# Single_Socket_TEMPORARY.net
KiCad netlist of a schematic drawn in EAGLE
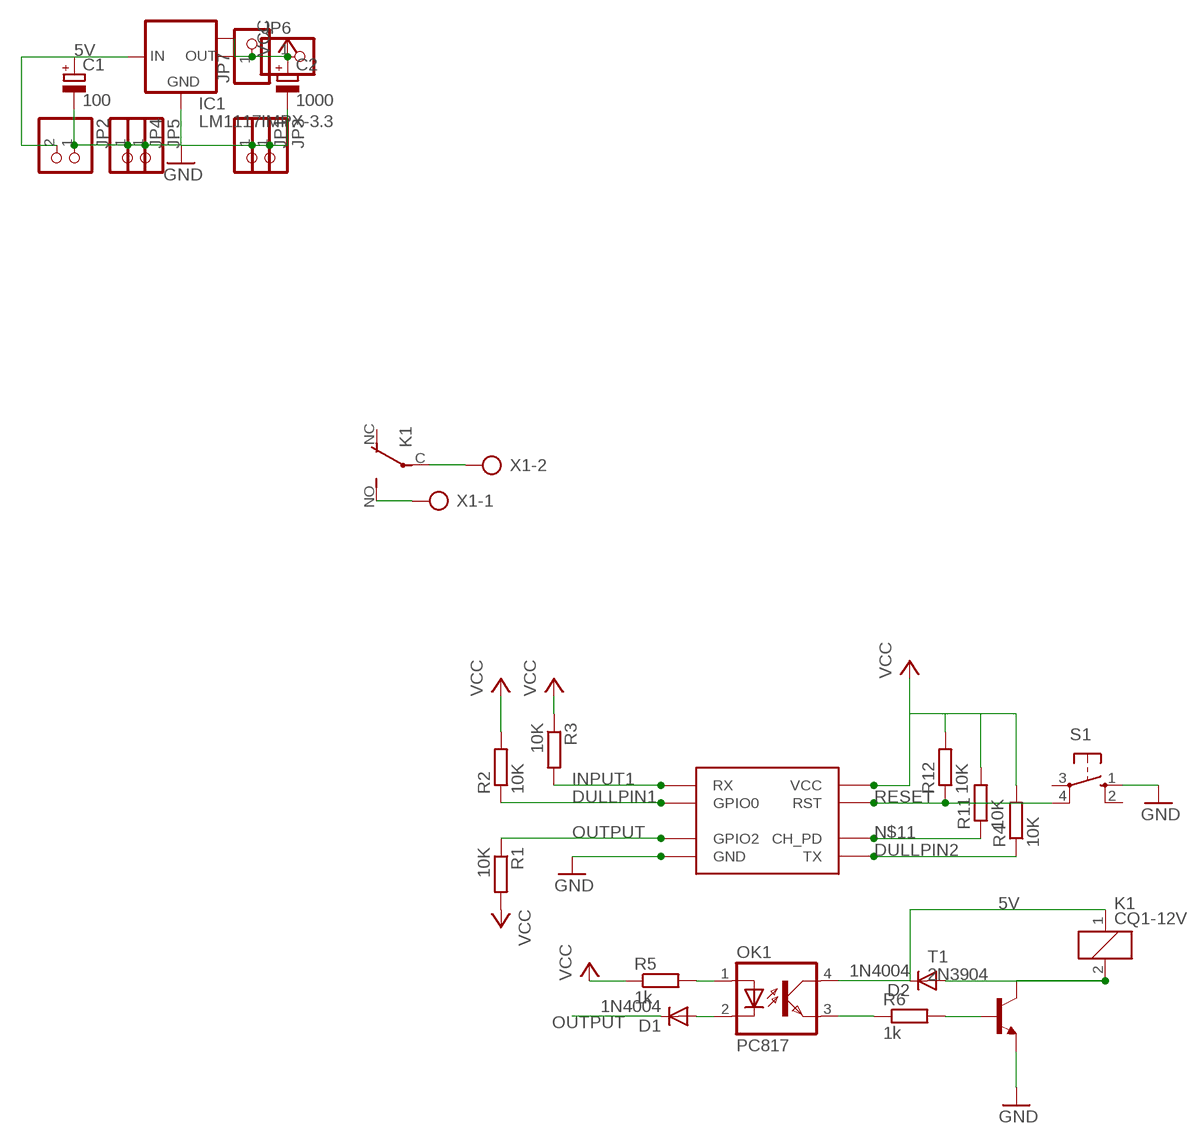
[diagram p0: schematic, sheet 1]

(export (version "E")
  (design (tool "Eeschema 10.0.6"))
  (components
    (comp (ref "C1")
      (value "100")
      (footprint "eagle-import:E5-10,5")
      (libsource (lib "eagle-import") (part "CPOL-EUE5-10.5"))
    )
    (comp (ref "C2")
      (value "1000")
      (footprint "eagle-import:E5-10,5")
      (libsource (lib "eagle-import") (part "CPOL-EUE5-10.5"))
    )
    (comp (ref "D1")
      (value "1N4004")
      (footprint "eagle-import:DO41-10")
      (libsource (lib "eagle-import") (part "1N4004"))
    )
    (comp (ref "D2")
      (value "1N4004")
      (footprint "eagle-import:DO41-10")
      (libsource (lib "eagle-import") (part "1N4004"))
    )
    (comp (ref "IC1")
      (value "LM1117IMPX-3.3")
      (footprint "eagle-import:SOT223")
      (libsource (lib "eagle-import") (part "LM1117IMPX-3.3"))
    )
    (comp (ref "JP1")
      (value "PINHD-1X1")
      (footprint "eagle-import:1X01")
      (libsource (lib "eagle-import") (part "PINHD-1X1"))
    )
    (comp (ref "JP2")
      (value "PINHD-1X2")
      (footprint "eagle-import:1X02")
      (libsource (lib "eagle-import") (part "PINHD-1X2"))
    )
    (comp (ref "JP3")
      (value "PINHD-1X1")
      (footprint "eagle-import:1X01")
      (libsource (lib "eagle-import") (part "PINHD-1X1"))
    )
    (comp (ref "JP4")
      (value "PINHD-1X1")
      (footprint "eagle-import:1X01")
      (libsource (lib "eagle-import") (part "PINHD-1X1"))
    )
    (comp (ref "JP5")
      (value "PINHD-1X1")
      (footprint "eagle-import:1X01")
      (libsource (lib "eagle-import") (part "PINHD-1X1"))
    )
    (comp (ref "JP6")
      (value "PINHD-1X1")
      (footprint "eagle-import:1X01")
      (libsource (lib "eagle-import") (part "PINHD-1X1"))
    )
    (comp (ref "JP7")
      (value "PINHD-1X1")
      (footprint "eagle-import:1X01")
      (libsource (lib "eagle-import") (part "PINHD-1X1"))
    )
    (comp (ref "K1")
      (value "CQ1-12V")
      (footprint "eagle-import:CQ1")
      (libsource (lib "eagle-import") (part "CQ1-12V"))
    )
    (comp (ref "OK1")
      (value "PC817")
      (footprint "eagle-import:DIL04")
      (fields (field (name "MPN") "PC817X4J000F"))
      (libsource (lib "eagle-import") (part "PC817"))
    )
    (comp (ref "R1")
      (value "10K")
      (footprint "eagle-import:0207_10")
      (libsource (lib "eagle-import") (part "R-EU_0207/10"))
    )
    (comp (ref "R2")
      (value "10K")
      (footprint "eagle-import:0207_10")
      (libsource (lib "eagle-import") (part "R-EU_0207/10"))
    )
    (comp (ref "R3")
      (value "10K")
      (footprint "eagle-import:0207_10")
      (libsource (lib "eagle-import") (part "R-EU_0207/10"))
    )
    (comp (ref "R4")
      (value "10K")
      (footprint "eagle-import:0207_10")
      (libsource (lib "eagle-import") (part "R-EU_0207/10"))
    )
    (comp (ref "R5")
      (value "1k")
      (footprint "eagle-import:0207_10")
      (libsource (lib "eagle-import") (part "R-EU_0207/10"))
    )
    (comp (ref "R6")
      (value "1k")
      (footprint "eagle-import:0207_10")
      (libsource (lib "eagle-import") (part "R-EU_0207/10"))
    )
    (comp (ref "R11")
      (value "10K")
      (footprint "eagle-import:0207_10")
      (libsource (lib "eagle-import") (part "R-EU_0207/10"))
    )
    (comp (ref "R12")
      (value "10K")
      (footprint "eagle-import:0207_10")
      (libsource (lib "eagle-import") (part "R-EU_0207/10"))
    )
    (comp (ref "S1")
      (value "10-XX")
      (footprint "eagle-import:B3F-10XX")
      (fields
        (field (name "MPN") "B3F-1000")
        (field (name "MPN_1") "B3F-1000")
        (field (name "OC_FARNELL") "176432")
        (field (name "OC_NEWARK") "36M3542")
      )
      (libsource (lib "eagle-import") (part "10-XX"))
    )
    (comp (ref "T1")
      (value "2N3904")
      (footprint "eagle-import:TO92")
      (libsource (lib "eagle-import") (part "2N3904"))
    )
    (comp (ref "U$2")
      (value "ESP8266")
      (footprint "eagle-import:ESP8266")
      (libsource (lib "eagle-import") (part "ESP8266"))
    )
    (comp (ref "X1")
      (value "AK500/2-H")
      (footprint "eagle-import:AK500_2-H")
      (libsource (lib "eagle-import") (part "AK500/2-H"))
    )
  )
  (nets
    (net (code "1") (name "/5V") (class "Default")
      (node (ref "C1") (pin "+") (pinfunction "+_+") (pintype "passive"))
      (node (ref "D2") (pin "C") (pinfunction "C_C") (pintype "passive"))
      (node (ref "IC1") (pin "3") (pinfunction "IN_3") (pintype "input"))
      (node (ref "JP2") (pin "2") (pinfunction "2_2") (pintype "passive"))
      (node (ref "K1") (pin "1") (pinfunction "1_1") (pintype "passive"))
      (node (ref "OK1") (pin "4") (pinfunction "COL_4") (pintype "passive"))
    )
    (net (code "2") (name "/DULLPIN1") (class "Default")
      (node (ref "R2") (pin "1") (pinfunction "1_1") (pintype "passive"))
      (node (ref "U$2") (pin "GPIO0") (pinfunction "GPIO0_GPIO0") (pintype "bidirectional"))
    )
    (net (code "3") (name "/DULLPIN2") (class "Default")
      (node (ref "R4") (pin "1") (pinfunction "1_1") (pintype "passive"))
      (node (ref "U$2") (pin "TX") (pinfunction "TX_TX") (pintype "bidirectional"))
    )
    (net (code "4") (name "/INPUT1") (class "Default")
      (node (ref "R3") (pin "2") (pinfunction "2_2") (pintype "passive"))
      (node (ref "U$2") (pin "RX") (pinfunction "RX_RX") (pintype "bidirectional"))
    )
    (net (code "5") (name "/N$11") (class "Default")
      (node (ref "R11") (pin "1") (pinfunction "1_1") (pintype "passive"))
      (node (ref "U$2") (pin "CH_PD") (pinfunction "CH_PD_CH_PD") (pintype "bidirectional"))
    )
    (net (code "6") (name "/OUTPUT") (class "Default")
      (node (ref "D1") (pin "C") (pinfunction "C_C") (pintype "passive"))
      (node (ref "R1") (pin "1") (pinfunction "1_1") (pintype "passive"))
      (node (ref "U$2") (pin "GPIO2") (pinfunction "GPIO2_GPIO2") (pintype "bidirectional"))
    )
    (net (code "7") (name "/RESET") (class "Default")
      (node (ref "R12") (pin "1") (pinfunction "1_1") (pintype "passive"))
      (node (ref "S1") (pin "4") (pinfunction "P1_4") (pintype "passive"))
      (node (ref "U$2") (pin "RST") (pinfunction "RST_RST") (pintype "bidirectional"))
    )
    (net (code "8") (name "GND") (class "Default")
      (node (ref "C1") (pin "-") (pinfunction "-_-") (pintype "passive"))
      (node (ref "C2") (pin "-") (pinfunction "-_-") (pintype "passive"))
      (node (ref "IC1") (pin "1") (pinfunction "GND_1") (pintype "input"))
      (node (ref "JP1") (pin "1") (pinfunction "1_1") (pintype "passive"))
      (node (ref "JP2") (pin "1") (pinfunction "1_1") (pintype "passive"))
      (node (ref "JP3") (pin "1") (pinfunction "1_1") (pintype "passive"))
      (node (ref "JP4") (pin "1") (pinfunction "1_1") (pintype "passive"))
      (node (ref "JP5") (pin "1") (pinfunction "1_1") (pintype "passive"))
      (node (ref "S1") (pin "1") (pinfunction "S_1") (pintype "passive"))
      (node (ref "T1") (pin "3") (pinfunction "E_3") (pintype "passive"))
      (node (ref "U$2") (pin "GND") (pinfunction "GND_GND") (pintype "bidirectional"))
    )
    (net (code "9") (name "Net-(K1B-P)") (class "Default")
      (node (ref "K1") (pin "C") (pinfunction "P_C") (pintype "passive"))
      (node (ref "X1") (pin "2") (pinfunction "KL_2") (pintype "passive"))
    )
    (net (code "10") (name "Net-(K1B-S)") (class "Default")
      (node (ref "K1") (pin "NO") (pinfunction "S_NO") (pintype "passive"))
      (node (ref "X1") (pin "1") (pinfunction "KL_1") (pintype "passive"))
    )
    (net (code "11") (name "Net-(OK1-A)") (class "Default")
      (node (ref "OK1") (pin "1") (pinfunction "A_1") (pintype "passive"))
      (node (ref "R5") (pin "2") (pinfunction "2_2") (pintype "passive"))
    )
    (net (code "12") (name "Net-(OK1-C)") (class "Default")
      (node (ref "D1") (pin "A") (pinfunction "A_A") (pintype "passive"))
      (node (ref "OK1") (pin "2") (pinfunction "C_2") (pintype "passive"))
    )
    (net (code "13") (name "Net-(OK1-EMIT)") (class "Default")
      (node (ref "OK1") (pin "3") (pinfunction "EMIT_3") (pintype "passive"))
      (node (ref "R6") (pin "1") (pinfunction "1_1") (pintype "passive"))
    )
    (net (code "14") (name "Net-(T1-B)") (class "Default")
      (node (ref "R6") (pin "2") (pinfunction "2_2") (pintype "passive"))
      (node (ref "T1") (pin "2") (pinfunction "B_2") (pintype "passive"))
    )
    (net (code "15") (name "Net-(T1-C)") (class "Default")
      (node (ref "D2") (pin "A") (pinfunction "A_A") (pintype "passive"))
      (node (ref "K1") (pin "2") (pinfunction "2_2") (pintype "passive"))
      (node (ref "T1") (pin "1") (pinfunction "C_1") (pintype "passive"))
    )
    (net (code "16") (name "VCC") (class "Default")
      (node (ref "C2") (pin "+") (pinfunction "+_+") (pintype "passive"))
      (node (ref "IC1") (pin "2") (pinfunction "OUT_2") (pintype "passive"))
      (node (ref "IC1") (pin "TAB") (pinfunction "OUT1_TAB") (pintype "passive"))
      (node (ref "JP6") (pin "1") (pinfunction "1_1") (pintype "passive"))
      (node (ref "JP7") (pin "1") (pinfunction "1_1") (pintype "passive"))
      (node (ref "R1") (pin "2") (pinfunction "2_2") (pintype "passive"))
      (node (ref "R11") (pin "2") (pinfunction "2_2") (pintype "passive"))
      (node (ref "R12") (pin "2") (pinfunction "2_2") (pintype "passive"))
      (node (ref "R2") (pin "2") (pinfunction "2_2") (pintype "passive"))
      (node (ref "R3") (pin "1") (pinfunction "1_1") (pintype "passive"))
      (node (ref "R4") (pin "2") (pinfunction "2_2") (pintype "passive"))
      (node (ref "R5") (pin "1") (pinfunction "1_1") (pintype "passive"))
      (node (ref "U$2") (pin "VCC") (pinfunction "VCC_VCC") (pintype "bidirectional"))
    )
    (net (code "17") (name "unconnected-(K1B-O-PadNC)") (class "Default")
      (node (ref "K1") (pin "NC") (pinfunction "O_NC") (pintype "passive"))
    )
    (net (code "18") (name "unconnected-(S1-P-Pad3)") (class "Default")
      (node (ref "S1") (pin "3") (pinfunction "P_3") (pintype "passive"))
    )
    (net (code "19") (name "unconnected-(S1-S1-Pad2)") (class "Default")
      (node (ref "S1") (pin "2") (pinfunction "S1_2") (pintype "passive"))
    )
  )
)
